# Pawmeat_Ton.net
KiCad netlist of a schematic drawn in EAGLE
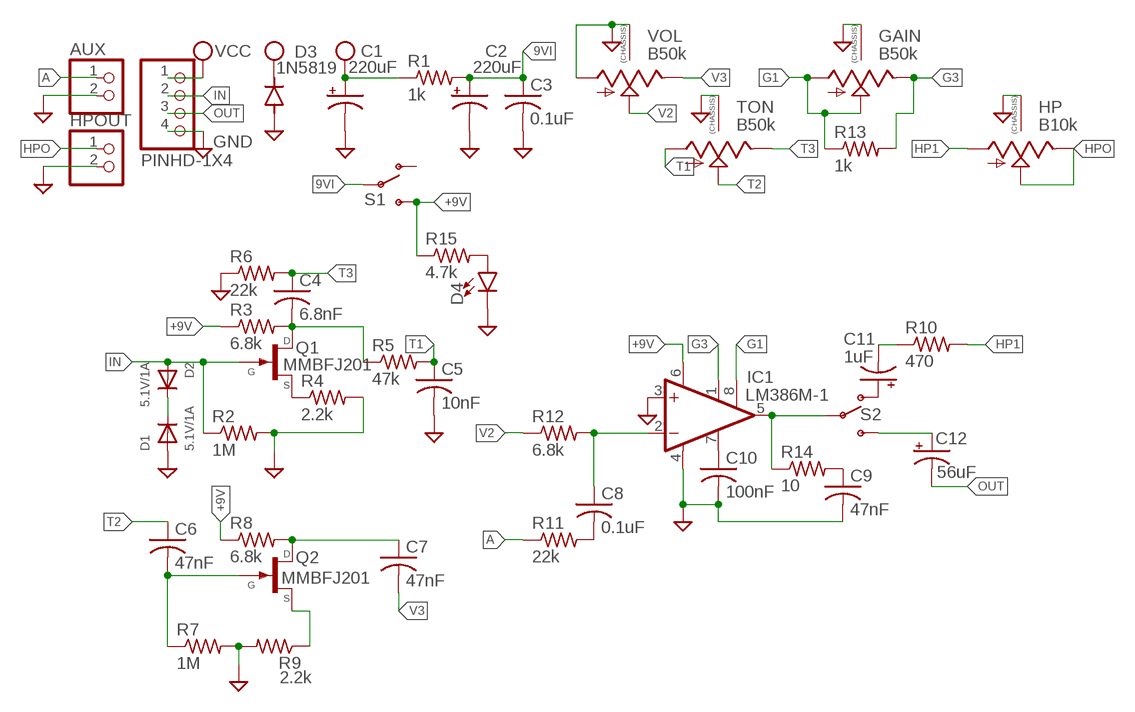
[diagram p0: schematic, sheet 1]

(export (version "E")
  (design (tool "Eeschema 10.0.6"))
  (components
    (comp (ref "AUX")
      (value "PINHD-1X2")
      (footprint "eagle-import:1X02")
      (libsource (lib "eagle-import") (part "PINHD-1X2"))
    )
    (comp (ref "C1")
      (value "220uF")
      (footprint "eagle-import:PAN_B_SMD+THRU")
      (libsource (lib "eagle-import") (part "CAP_SMD+THRUPAN_B"))
    )
    (comp (ref "C2")
      (value "220uF")
      (footprint "eagle-import:PAN_B_SMD+THRU")
      (libsource (lib "eagle-import") (part "CAP_SMD+THRUPAN_B"))
    )
    (comp (ref "C3")
      (value "0.1uF")
      (footprint "eagle-import:C0402")
      (libsource (lib "eagle-import") (part "C-USC0402"))
    )
    (comp (ref "C4")
      (value "6.8nF")
      (footprint "eagle-import:C0402")
      (libsource (lib "eagle-import") (part "C-USC0402"))
    )
    (comp (ref "C5")
      (value "10nF")
      (footprint "eagle-import:C0402")
      (libsource (lib "eagle-import") (part "C-USC0402"))
    )
    (comp (ref "C6")
      (value "47nF")
      (footprint "eagle-import:C0402")
      (libsource (lib "eagle-import") (part "C-USC0402"))
    )
    (comp (ref "C7")
      (value "47nF")
      (footprint "eagle-import:C0402")
      (libsource (lib "eagle-import") (part "C-USC0402"))
    )
    (comp (ref "C8")
      (value "0.1uF")
      (footprint "eagle-import:C0402")
      (libsource (lib "eagle-import") (part "C-USC0402"))
    )
    (comp (ref "C9")
      (value "47nF")
      (footprint "eagle-import:C0402")
      (libsource (lib "eagle-import") (part "C-USC0402"))
    )
    (comp (ref "C10")
      (value "100nF")
      (footprint "eagle-import:C0402")
      (libsource (lib "eagle-import") (part "C-USC0402"))
    )
    (comp (ref "C11")
      (value "1uF")
      (footprint "eagle-import:PAN_B_SMD+THRU")
      (libsource (lib "eagle-import") (part "CAP_SMD+THRUPAN_B"))
    )
    (comp (ref "C12")
      (value "56uF")
      (footprint "eagle-import:PAN_B_SMD+THRU")
      (libsource (lib "eagle-import") (part "CAP_SMD+THRUPAN_B"))
    )
    (comp (ref "D1")
      (value "5.1V/1A")
      (footprint "eagle-import:SMADIODE")
      (libsource (lib "eagle-import") (part "DIODESMA"))
    )
    (comp (ref "D2")
      (value "5.1V/1A")
      (footprint "eagle-import:SMADIODE")
      (libsource (lib "eagle-import") (part "DIODESMA"))
    )
    (comp (ref "D3")
      (value "1N5819")
      (footprint "eagle-import:SOD123")
      (libsource (lib "eagle-import") (part "DIODE-SOD123"))
    )
    (comp (ref "D4")
      (value "LED0603")
      (footprint "eagle-import:LED-0603")
      (libsource (lib "eagle-import") (part "LED0603"))
    )
    (comp (ref "GAIN")
      (value "B50k")
      (footprint "eagle-import:9MM_SNAP-IN_POT")
      (libsource (lib "eagle-import") (part "9MM_SNAP-IN_POT_CHASSIS"))
    )
    (comp (ref "HP")
      (value "B10k")
      (footprint "eagle-import:9MM_SNAP-IN_POT")
      (libsource (lib "eagle-import") (part "9MM_SNAP-IN_POT_CHASSIS"))
    )
    (comp (ref "HPOUT")
      (value "PINHD-1X2")
      (footprint "eagle-import:1X02")
      (libsource (lib "eagle-import") (part "PINHD-1X2"))
    )
    (comp (ref "IC1")
      (value "LM386M-1")
      (footprint "eagle-import:SO08")
      (libsource (lib "eagle-import") (part "LM386?-M1"))
    )
    (comp (ref "JP1")
      (value "PINHD-1X4")
      (footprint "eagle-import:1X04")
      (libsource (lib "eagle-import") (part "PINHD-1X4"))
    )
    (comp (ref "Q1")
      (value "MMBFJ201")
      (footprint "eagle-import:SOT23")
      (fields (field (name "MF") "ON Semiconductor") (field (name "MP") "MMBF5457"))
      (libsource (lib "eagle-import") (part "MMBF5457"))
    )
    (comp (ref "Q2")
      (value "MMBFJ201")
      (footprint "eagle-import:SOT23")
      (fields (field (name "MF") "ON Semiconductor") (field (name "MP") "MMBF5457"))
      (libsource (lib "eagle-import") (part "MMBF5457"))
    )
    (comp (ref "R1")
      (value "1k")
      (footprint "eagle-import:R0402")
      (libsource (lib "eagle-import") (part "R-US_R0402"))
    )
    (comp (ref "R2")
      (value "1M")
      (footprint "eagle-import:R0402")
      (libsource (lib "eagle-import") (part "R-US_R0402"))
    )
    (comp (ref "R3")
      (value "6.8k")
      (footprint "eagle-import:R0402")
      (libsource (lib "eagle-import") (part "R-US_R0402"))
    )
    (comp (ref "R4")
      (value "2.2k")
      (footprint "eagle-import:R0402")
      (libsource (lib "eagle-import") (part "R-US_R0402"))
    )
    (comp (ref "R5")
      (value "47k")
      (footprint "eagle-import:R0402")
      (libsource (lib "eagle-import") (part "R-US_R0402"))
    )
    (comp (ref "R6")
      (value "22k")
      (footprint "eagle-import:R0402")
      (libsource (lib "eagle-import") (part "R-US_R0402"))
    )
    (comp (ref "R7")
      (value "1M")
      (footprint "eagle-import:R0402")
      (libsource (lib "eagle-import") (part "R-US_R0402"))
    )
    (comp (ref "R8")
      (value "6.8k")
      (footprint "eagle-import:R0402")
      (libsource (lib "eagle-import") (part "R-US_R0402"))
    )
    (comp (ref "R9")
      (value "2.2k")
      (footprint "eagle-import:R0402")
      (libsource (lib "eagle-import") (part "R-US_R0402"))
    )
    (comp (ref "R10")
      (value "470")
      (footprint "eagle-import:R0402")
      (libsource (lib "eagle-import") (part "R-US_R0402"))
    )
    (comp (ref "R11")
      (value "22k")
      (footprint "eagle-import:R0402")
      (libsource (lib "eagle-import") (part "R-US_R0402"))
    )
    (comp (ref "R12")
      (value "6.8k")
      (footprint "eagle-import:R0402")
      (libsource (lib "eagle-import") (part "R-US_R0402"))
    )
    (comp (ref "R13")
      (value "1k")
      (footprint "eagle-import:R0402")
      (libsource (lib "eagle-import") (part "R-US_R0402"))
    )
    (comp (ref "R14")
      (value "10")
      (footprint "eagle-import:R0402")
      (libsource (lib "eagle-import") (part "R-US_R0402"))
    )
    (comp (ref "R15")
      (value "4.7k")
      (footprint "eagle-import:R0402")
      (libsource (lib "eagle-import") (part "R-US_R0402"))
    )
    (comp (ref "S1")
      (value "SWITCH-SPDTSMD2")
      (footprint "eagle-import:SWITCH-SPDT-SMD")
      (libsource (lib "eagle-import") (part "SWITCH-SPDTSMD2"))
    )
    (comp (ref "S2")
      (value "SWITCH-SPDTSMD2")
      (footprint "eagle-import:SWITCH-SPDT-SMD")
      (libsource (lib "eagle-import") (part "SWITCH-SPDTSMD2"))
    )
    (comp (ref "TON")
      (value "B50k")
      (footprint "eagle-import:9MM_SNAP-IN_POT")
      (libsource (lib "eagle-import") (part "9MM_SNAP-IN_POT_CHASSIS"))
    )
    (comp (ref "VOL")
      (value "B50k")
      (footprint "eagle-import:9MM_SNAP-IN_POT")
      (libsource (lib "eagle-import") (part "9MM_SNAP-IN_POT_CHASSIS"))
    )
  )
  (nets
    (net (code "1") (name "+9V") (class "Default")
      (node (ref "IC1") (pin "6") (pinfunction "VS_6") (pintype "power_in"))
      (node (ref "R15") (pin "1") (pinfunction "1_1") (pintype "passive"))
      (node (ref "R3") (pin "1") (pinfunction "1_1") (pintype "passive"))
      (node (ref "R8") (pin "1") (pinfunction "1_1") (pintype "passive"))
      (node (ref "S1") (pin "3") (pinfunction "S_3") (pintype "passive"))
    )
    (net (code "2") (name "9VI") (class "Default")
      (node (ref "C2") (pin "+") (pinfunction "+_+") (pintype "passive"))
      (node (ref "C2") (pin "++") (pinfunction "+_++") (pintype "passive"))
      (node (ref "C3") (pin "1") (pinfunction "1_1") (pintype "passive"))
      (node (ref "R1") (pin "2") (pinfunction "2_2") (pintype "passive"))
      (node (ref "S1") (pin "2") (pinfunction "P_2") (pintype "passive"))
    )
    (net (code "3") (name "A") (class "Default")
      (node (ref "AUX") (pin "1") (pinfunction "1_1") (pintype "passive"))
      (node (ref "R11") (pin "1") (pinfunction "1_1") (pintype "passive"))
    )
    (net (code "4") (name "G1") (class "Default")
      (node (ref "GAIN") (pin "1") (pinfunction "A_1") (pintype "passive"))
      (node (ref "GAIN") (pin "2") (pinfunction "S_2") (pintype "passive"))
      (node (ref "IC1") (pin "8") (pinfunction "GAIN_8") (pintype "passive"))
      (node (ref "R13") (pin "1") (pinfunction "1_1") (pintype "passive"))
    )
    (net (code "5") (name "G3") (class "Default")
      (node (ref "GAIN") (pin "3") (pinfunction "E_3") (pintype "passive"))
      (node (ref "IC1") (pin "1") (pinfunction "GAIN_1") (pintype "passive"))
      (node (ref "R13") (pin "2") (pinfunction "2_2") (pintype "passive"))
    )
    (net (code "6") (name "GND") (class "Default")
      (node (ref "AUX") (pin "2") (pinfunction "2_2") (pintype "passive"))
      (node (ref "C1") (pin "-") (pinfunction "-_-") (pintype "passive"))
      (node (ref "C1") (pin "--") (pinfunction "-_--") (pintype "passive"))
      (node (ref "C10") (pin "2") (pinfunction "2_2") (pintype "passive"))
      (node (ref "C2") (pin "-") (pinfunction "-_-") (pintype "passive"))
      (node (ref "C2") (pin "--") (pinfunction "-_--") (pintype "passive"))
      (node (ref "C3") (pin "2") (pinfunction "2_2") (pintype "passive"))
      (node (ref "C5") (pin "2") (pinfunction "2_2") (pintype "passive"))
      (node (ref "C9") (pin "2") (pinfunction "2_2") (pintype "passive"))
      (node (ref "D1") (pin "A") (pinfunction "A_A") (pintype "passive"))
      (node (ref "D3") (pin "A") (pinfunction "A_A") (pintype "passive"))
      (node (ref "D4") (pin "C") (pinfunction "C_C") (pintype "passive"))
      (node (ref "GAIN") (pin "CHASSIS1") (pinfunction "P$1_CHASSIS1") (pintype "passive"))
      (node (ref "GAIN") (pin "CHASSIS2") (pinfunction "P$1_CHASSIS2") (pintype "passive"))
      (node (ref "HP") (pin "CHASSIS1") (pinfunction "P$1_CHASSIS1") (pintype "passive"))
      (node (ref "HP") (pin "CHASSIS2") (pinfunction "P$1_CHASSIS2") (pintype "passive"))
      (node (ref "HPOUT") (pin "2") (pinfunction "2_2") (pintype "passive"))
      (node (ref "IC1") (pin "3") (pinfunction "+IN_3") (pintype "input"))
      (node (ref "IC1") (pin "4") (pinfunction "GND_4") (pintype "power_in"))
      (node (ref "JP1") (pin "4") (pinfunction "4_4") (pintype "passive"))
      (node (ref "R2") (pin "2") (pinfunction "2_2") (pintype "passive"))
      (node (ref "R4") (pin "2") (pinfunction "2_2") (pintype "passive"))
      (node (ref "R6") (pin "1") (pinfunction "1_1") (pintype "passive"))
      (node (ref "R7") (pin "2") (pinfunction "2_2") (pintype "passive"))
      (node (ref "R9") (pin "2") (pinfunction "2_2") (pintype "passive"))
      (node (ref "TON") (pin "CHASSIS1") (pinfunction "P$1_CHASSIS1") (pintype "passive"))
      (node (ref "TON") (pin "CHASSIS2") (pinfunction "P$1_CHASSIS2") (pintype "passive"))
      (node (ref "VOL") (pin "1") (pinfunction "A_1") (pintype "passive"))
      (node (ref "VOL") (pin "CHASSIS1") (pinfunction "P$1_CHASSIS1") (pintype "passive"))
      (node (ref "VOL") (pin "CHASSIS2") (pinfunction "P$1_CHASSIS2") (pintype "passive"))
    )
    (net (code "7") (name "HP1") (class "Default")
      (node (ref "HP") (pin "1") (pinfunction "A_1") (pintype "passive"))
      (node (ref "R10") (pin "2") (pinfunction "2_2") (pintype "passive"))
    )
    (net (code "8") (name "HPO") (class "Default")
      (node (ref "HP") (pin "2") (pinfunction "S_2") (pintype "passive"))
      (node (ref "HP") (pin "3") (pinfunction "E_3") (pintype "passive"))
      (node (ref "HPOUT") (pin "1") (pinfunction "1_1") (pintype "passive"))
    )
    (net (code "9") (name "IN") (class "Default")
      (node (ref "D2") (pin "A") (pinfunction "A_A") (pintype "passive"))
      (node (ref "JP1") (pin "2") (pinfunction "2_2") (pintype "passive"))
      (node (ref "Q1") (pin "3") (pinfunction "G_3") (pintype "passive"))
      (node (ref "R2") (pin "1") (pinfunction "1_1") (pintype "passive"))
    )
    (net (code "10") (name "Net-(C8-Pad2)") (class "Default")
      (node (ref "C8") (pin "2") (pinfunction "2_2") (pintype "passive"))
      (node (ref "R11") (pin "2") (pinfunction "2_2") (pintype "passive"))
    )
    (net (code "11") (name "Net-(C9-Pad1)") (class "Default")
      (node (ref "C9") (pin "1") (pinfunction "1_1") (pintype "passive"))
      (node (ref "R14") (pin "2") (pinfunction "2_2") (pintype "passive"))
    )
    (net (code "12") (name "Net-(C11---Pad--)") (class "Default")
      (node (ref "C11") (pin "-") (pinfunction "-_-") (pintype "passive"))
      (node (ref "C11") (pin "--") (pinfunction "-_--") (pintype "passive"))
      (node (ref "R10") (pin "1") (pinfunction "1_1") (pintype "passive"))
    )
    (net (code "13") (name "Net-(D1-PadC)") (class "Default")
      (node (ref "D1") (pin "C") (pinfunction "C_C") (pintype "passive"))
      (node (ref "D2") (pin "C") (pinfunction "C_C") (pintype "passive"))
    )
    (net (code "14") (name "Net-(D4-PadA)") (class "Default")
      (node (ref "D4") (pin "A") (pinfunction "A_A") (pintype "passive"))
      (node (ref "R15") (pin "2") (pinfunction "2_2") (pintype "passive"))
    )
    (net (code "15") (name "Net-(IC1--IN)") (class "Default")
      (node (ref "C8") (pin "1") (pinfunction "1_1") (pintype "passive"))
      (node (ref "IC1") (pin "2") (pinfunction "-IN_2") (pintype "input"))
      (node (ref "R12") (pin "2") (pinfunction "2_2") (pintype "passive"))
    )
    (net (code "16") (name "Net-(IC1-BYPASS)") (class "Default")
      (node (ref "C10") (pin "1") (pinfunction "1_1") (pintype "passive"))
      (node (ref "IC1") (pin "7") (pinfunction "BYPASS_7") (pintype "passive"))
    )
    (net (code "17") (name "Net-(IC1-OUT)") (class "Default")
      (node (ref "IC1") (pin "5") (pinfunction "OUT_5") (pintype "output"))
      (node (ref "R14") (pin "1") (pinfunction "1_1") (pintype "passive"))
      (node (ref "S2") (pin "2") (pinfunction "P_2") (pintype "passive"))
    )
    (net (code "18") (name "Net-(Q1-D)") (class "Default")
      (node (ref "C4") (pin "2") (pinfunction "2_2") (pintype "passive"))
      (node (ref "Q1") (pin "1") (pinfunction "D_1") (pintype "passive"))
      (node (ref "R3") (pin "2") (pinfunction "2_2") (pintype "passive"))
      (node (ref "R5") (pin "1") (pinfunction "1_1") (pintype "passive"))
    )
    (net (code "19") (name "Net-(Q1-S)") (class "Default")
      (node (ref "Q1") (pin "2") (pinfunction "S_2") (pintype "passive"))
      (node (ref "R4") (pin "1") (pinfunction "1_1") (pintype "passive"))
    )
    (net (code "20") (name "Net-(Q2-D)") (class "Default")
      (node (ref "C7") (pin "1") (pinfunction "1_1") (pintype "passive"))
      (node (ref "Q2") (pin "1") (pinfunction "D_1") (pintype "passive"))
      (node (ref "R8") (pin "2") (pinfunction "2_2") (pintype "passive"))
    )
    (net (code "21") (name "Net-(Q2-G)") (class "Default")
      (node (ref "C6") (pin "2") (pinfunction "2_2") (pintype "passive"))
      (node (ref "Q2") (pin "3") (pinfunction "G_3") (pintype "passive"))
      (node (ref "R7") (pin "1") (pinfunction "1_1") (pintype "passive"))
    )
    (net (code "22") (name "Net-(Q2-S)") (class "Default")
      (node (ref "Q2") (pin "2") (pinfunction "S_2") (pintype "passive"))
      (node (ref "R9") (pin "1") (pinfunction "1_1") (pintype "passive"))
    )
    (net (code "23") (name "Net-(S2-O)") (class "Default")
      (node (ref "C11") (pin "+") (pinfunction "+_+") (pintype "passive"))
      (node (ref "C11") (pin "++") (pinfunction "+_++") (pintype "passive"))
      (node (ref "S2") (pin "1") (pinfunction "O_1") (pintype "passive"))
    )
    (net (code "24") (name "Net-(S2-S)") (class "Default")
      (node (ref "C12") (pin "+") (pinfunction "+_+") (pintype "passive"))
      (node (ref "C12") (pin "++") (pinfunction "+_++") (pintype "passive"))
      (node (ref "S2") (pin "3") (pinfunction "S_3") (pintype "passive"))
    )
    (net (code "25") (name "OUT") (class "Default")
      (node (ref "C12") (pin "-") (pinfunction "-_-") (pintype "passive"))
      (node (ref "C12") (pin "--") (pinfunction "-_--") (pintype "passive"))
      (node (ref "JP1") (pin "3") (pinfunction "3_3") (pintype "passive"))
    )
    (net (code "26") (name "T1") (class "Default")
      (node (ref "C5") (pin "1") (pinfunction "1_1") (pintype "passive"))
      (node (ref "R5") (pin "2") (pinfunction "2_2") (pintype "passive"))
      (node (ref "TON") (pin "1") (pinfunction "A_1") (pintype "passive"))
    )
    (net (code "27") (name "T2") (class "Default")
      (node (ref "C6") (pin "1") (pinfunction "1_1") (pintype "passive"))
      (node (ref "TON") (pin "2") (pinfunction "S_2") (pintype "passive"))
    )
    (net (code "28") (name "T3") (class "Default")
      (node (ref "C4") (pin "1") (pinfunction "1_1") (pintype "passive"))
      (node (ref "R6") (pin "2") (pinfunction "2_2") (pintype "passive"))
      (node (ref "TON") (pin "3") (pinfunction "E_3") (pintype "passive"))
    )
    (net (code "29") (name "V2") (class "Default")
      (node (ref "R12") (pin "1") (pinfunction "1_1") (pintype "passive"))
      (node (ref "VOL") (pin "2") (pinfunction "S_2") (pintype "passive"))
    )
    (net (code "30") (name "V3") (class "Default")
      (node (ref "C7") (pin "2") (pinfunction "2_2") (pintype "passive"))
      (node (ref "VOL") (pin "3") (pinfunction "E_3") (pintype "passive"))
    )
    (net (code "31") (name "VCC") (class "Default")
      (node (ref "C1") (pin "+") (pinfunction "+_+") (pintype "passive"))
      (node (ref "C1") (pin "++") (pinfunction "+_++") (pintype "passive"))
      (node (ref "D3") (pin "C") (pinfunction "C_C") (pintype "passive"))
      (node (ref "JP1") (pin "1") (pinfunction "1_1") (pintype "passive"))
      (node (ref "R1") (pin "1") (pinfunction "1_1") (pintype "passive"))
    )
    (net (code "32") (name "unconnected-(S1-O-Pad1)") (class "Default")
      (node (ref "S1") (pin "1") (pinfunction "O_1") (pintype "passive"))
    )
  )
)
